# slave.net
KiCad netlist of a schematic drawn in EAGLE
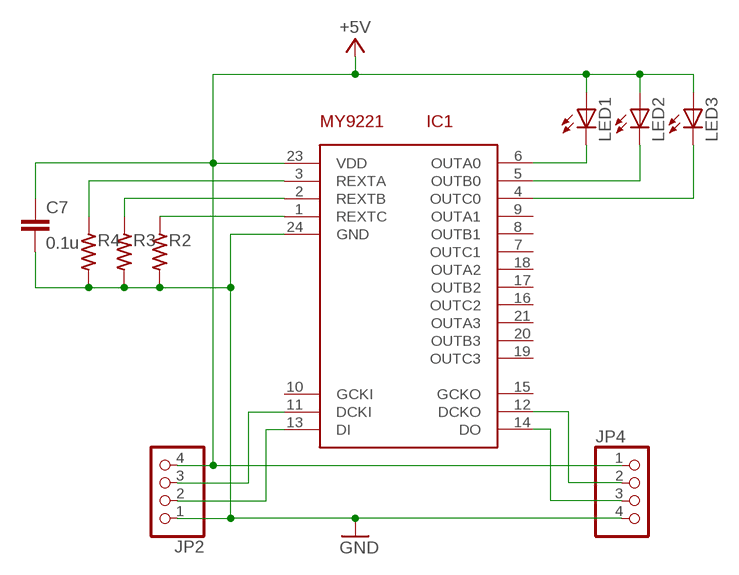
[diagram p0: schematic, sheet 1]

(export (version "E")
  (design (tool "Eeschema 10.0.6"))
  (components
    (comp (ref "C7")
      (value "0.1u")
      (footprint "eagle-import:C1608")
      (libsource (lib "eagle-import") (part "C-EUC1608"))
    )
    (comp (ref "IC1")
      (value "MY9221SS")
      (footprint "eagle-import:SSOP24")
      (libsource (lib "eagle-import") (part "MY9221SS"))
    )
    (comp (ref "JP2")
      (value "PINHD-1X4")
      (footprint "eagle-import:1X04")
      (libsource (lib "eagle-import") (part "PINHD-1X4"))
    )
    (comp (ref "JP4")
      (value "PINHD-1X4")
      (footprint "eagle-import:1X04")
      (libsource (lib "eagle-import") (part "PINHD-1X4"))
    )
    (comp (ref "LED1")
      (value "LED5MM")
      (footprint "eagle-import:LED5MM")
      (libsource (lib "eagle-import") (part "LED5MM"))
    )
    (comp (ref "LED2")
      (value "LED5MM")
      (footprint "eagle-import:LED5MM")
      (libsource (lib "eagle-import") (part "LED5MM"))
    )
    (comp (ref "LED3")
      (value "LED5MM")
      (footprint "eagle-import:LED5MM")
      (libsource (lib "eagle-import") (part "LED5MM"))
    )
    (comp (ref "R2")
      (value "RESISTOR-US1608")
      (footprint "eagle-import:SMD1608")
      (libsource (lib "eagle-import") (part "RESISTOR-US1608"))
    )
    (comp (ref "R3")
      (value "RESISTOR-US1608")
      (footprint "eagle-import:SMD1608")
      (libsource (lib "eagle-import") (part "RESISTOR-US1608"))
    )
    (comp (ref "R4")
      (value "RESISTOR-US1608")
      (footprint "eagle-import:SMD1608")
      (libsource (lib "eagle-import") (part "RESISTOR-US1608"))
    )
  )
  (nets
    (net (code "1") (name "+5V") (class "Default")
      (node (ref "C7") (pin "1") (pinfunction "1_1") (pintype "passive"))
      (node (ref "IC1") (pin "23") (pinfunction "VDD_23") (pintype "power_in"))
      (node (ref "JP2") (pin "4") (pinfunction "4_4") (pintype "passive"))
      (node (ref "JP4") (pin "1") (pinfunction "1_1") (pintype "passive"))
      (node (ref "LED1") (pin "A") (pinfunction "A_A") (pintype "passive"))
      (node (ref "LED2") (pin "A") (pinfunction "A_A") (pintype "passive"))
      (node (ref "LED3") (pin "A") (pinfunction "A_A") (pintype "passive"))
    )
    (net (code "2") (name "GND") (class "Default")
      (node (ref "C7") (pin "2") (pinfunction "2_2") (pintype "passive"))
      (node (ref "IC1") (pin "24") (pinfunction "GND_24") (pintype "power_in"))
      (node (ref "JP2") (pin "1") (pinfunction "1_1") (pintype "passive"))
      (node (ref "JP4") (pin "4") (pinfunction "4_4") (pintype "passive"))
      (node (ref "R2") (pin "2") (pinfunction "2_2") (pintype "passive"))
      (node (ref "R3") (pin "2") (pinfunction "2_2") (pintype "passive"))
      (node (ref "R4") (pin "2") (pinfunction "2_2") (pintype "passive"))
    )
    (net (code "3") (name "Net-(IC1-DCKI)") (class "Default")
      (node (ref "IC1") (pin "11") (pinfunction "DCKI_11") (pintype "input"))
      (node (ref "JP2") (pin "3") (pinfunction "3_3") (pintype "passive"))
    )
    (net (code "4") (name "Net-(IC1-DCKO)") (class "Default")
      (node (ref "IC1") (pin "12") (pinfunction "DCKO_12") (pintype "output"))
      (node (ref "JP4") (pin "2") (pinfunction "2_2") (pintype "passive"))
    )
    (net (code "5") (name "Net-(IC1-DI)") (class "Default")
      (node (ref "IC1") (pin "13") (pinfunction "DI_13") (pintype "input"))
      (node (ref "JP2") (pin "2") (pinfunction "2_2") (pintype "passive"))
    )
    (net (code "6") (name "Net-(IC1-DO)") (class "Default")
      (node (ref "IC1") (pin "14") (pinfunction "DO_14") (pintype "output"))
      (node (ref "JP4") (pin "3") (pinfunction "3_3") (pintype "passive"))
    )
    (net (code "7") (name "Net-(IC1-OUTA0)") (class "Default")
      (node (ref "IC1") (pin "6") (pinfunction "OUTA0_6") (pintype "open_collector"))
      (node (ref "LED1") (pin "K") (pinfunction "C_K") (pintype "passive"))
    )
    (net (code "8") (name "Net-(IC1-OUTB0)") (class "Default")
      (node (ref "IC1") (pin "5") (pinfunction "OUTB0_5") (pintype "open_collector"))
      (node (ref "LED2") (pin "K") (pinfunction "C_K") (pintype "passive"))
    )
    (net (code "9") (name "Net-(IC1-OUTC0)") (class "Default")
      (node (ref "IC1") (pin "4") (pinfunction "OUTC0_4") (pintype "open_collector"))
      (node (ref "LED3") (pin "K") (pinfunction "C_K") (pintype "passive"))
    )
    (net (code "10") (name "Net-(IC1-REXTA)") (class "Default")
      (node (ref "IC1") (pin "3") (pinfunction "REXTA_3") (pintype "input"))
      (node (ref "R4") (pin "1") (pinfunction "1_1") (pintype "passive"))
    )
    (net (code "11") (name "Net-(IC1-REXTB)") (class "Default")
      (node (ref "IC1") (pin "2") (pinfunction "REXTB_2") (pintype "input"))
      (node (ref "R3") (pin "1") (pinfunction "1_1") (pintype "passive"))
    )
    (net (code "12") (name "Net-(IC1-REXTC)") (class "Default")
      (node (ref "IC1") (pin "1") (pinfunction "REXTC_1") (pintype "input"))
      (node (ref "R2") (pin "1") (pinfunction "1_1") (pintype "passive"))
    )
    (net (code "13") (name "unconnected-(IC1-GCKI-Pad10)") (class "Default")
      (node (ref "IC1") (pin "10") (pinfunction "GCKI_10") (pintype "input"))
    )
    (net (code "14") (name "unconnected-(IC1-GCKO-Pad15)") (class "Default")
      (node (ref "IC1") (pin "15") (pinfunction "GCKO_15") (pintype "output"))
    )
    (net (code "15") (name "unconnected-(IC1-OUTA1-Pad9)") (class "Default")
      (node (ref "IC1") (pin "9") (pinfunction "OUTA1_9") (pintype "open_collector"))
    )
    (net (code "16") (name "unconnected-(IC1-OUTA2-Pad18)") (class "Default")
      (node (ref "IC1") (pin "18") (pinfunction "OUTA2_18") (pintype "open_collector"))
    )
    (net (code "17") (name "unconnected-(IC1-OUTA3-Pad21)") (class "Default")
      (node (ref "IC1") (pin "21") (pinfunction "OUTA3_21") (pintype "open_collector"))
    )
    (net (code "18") (name "unconnected-(IC1-OUTB1-Pad8)") (class "Default")
      (node (ref "IC1") (pin "8") (pinfunction "OUTB1_8") (pintype "open_collector"))
    )
    (net (code "19") (name "unconnected-(IC1-OUTB2-Pad17)") (class "Default")
      (node (ref "IC1") (pin "17") (pinfunction "OUTB2_17") (pintype "open_collector"))
    )
    (net (code "20") (name "unconnected-(IC1-OUTB3-Pad20)") (class "Default")
      (node (ref "IC1") (pin "20") (pinfunction "OUTB3_20") (pintype "open_collector"))
    )
    (net (code "21") (name "unconnected-(IC1-OUTC1-Pad7)") (class "Default")
      (node (ref "IC1") (pin "7") (pinfunction "OUTC1_7") (pintype "open_collector"))
    )
    (net (code "22") (name "unconnected-(IC1-OUTC2-Pad16)") (class "Default")
      (node (ref "IC1") (pin "16") (pinfunction "OUTC2_16") (pintype "open_collector"))
    )
    (net (code "23") (name "unconnected-(IC1-OUTC3-Pad19)") (class "Default")
      (node (ref "IC1") (pin "19") (pinfunction "OUTC3_19") (pintype "open_collector"))
    )
  )
)
